# LaserScanner.net
KiCad netlist of a schematic drawn in EAGLE
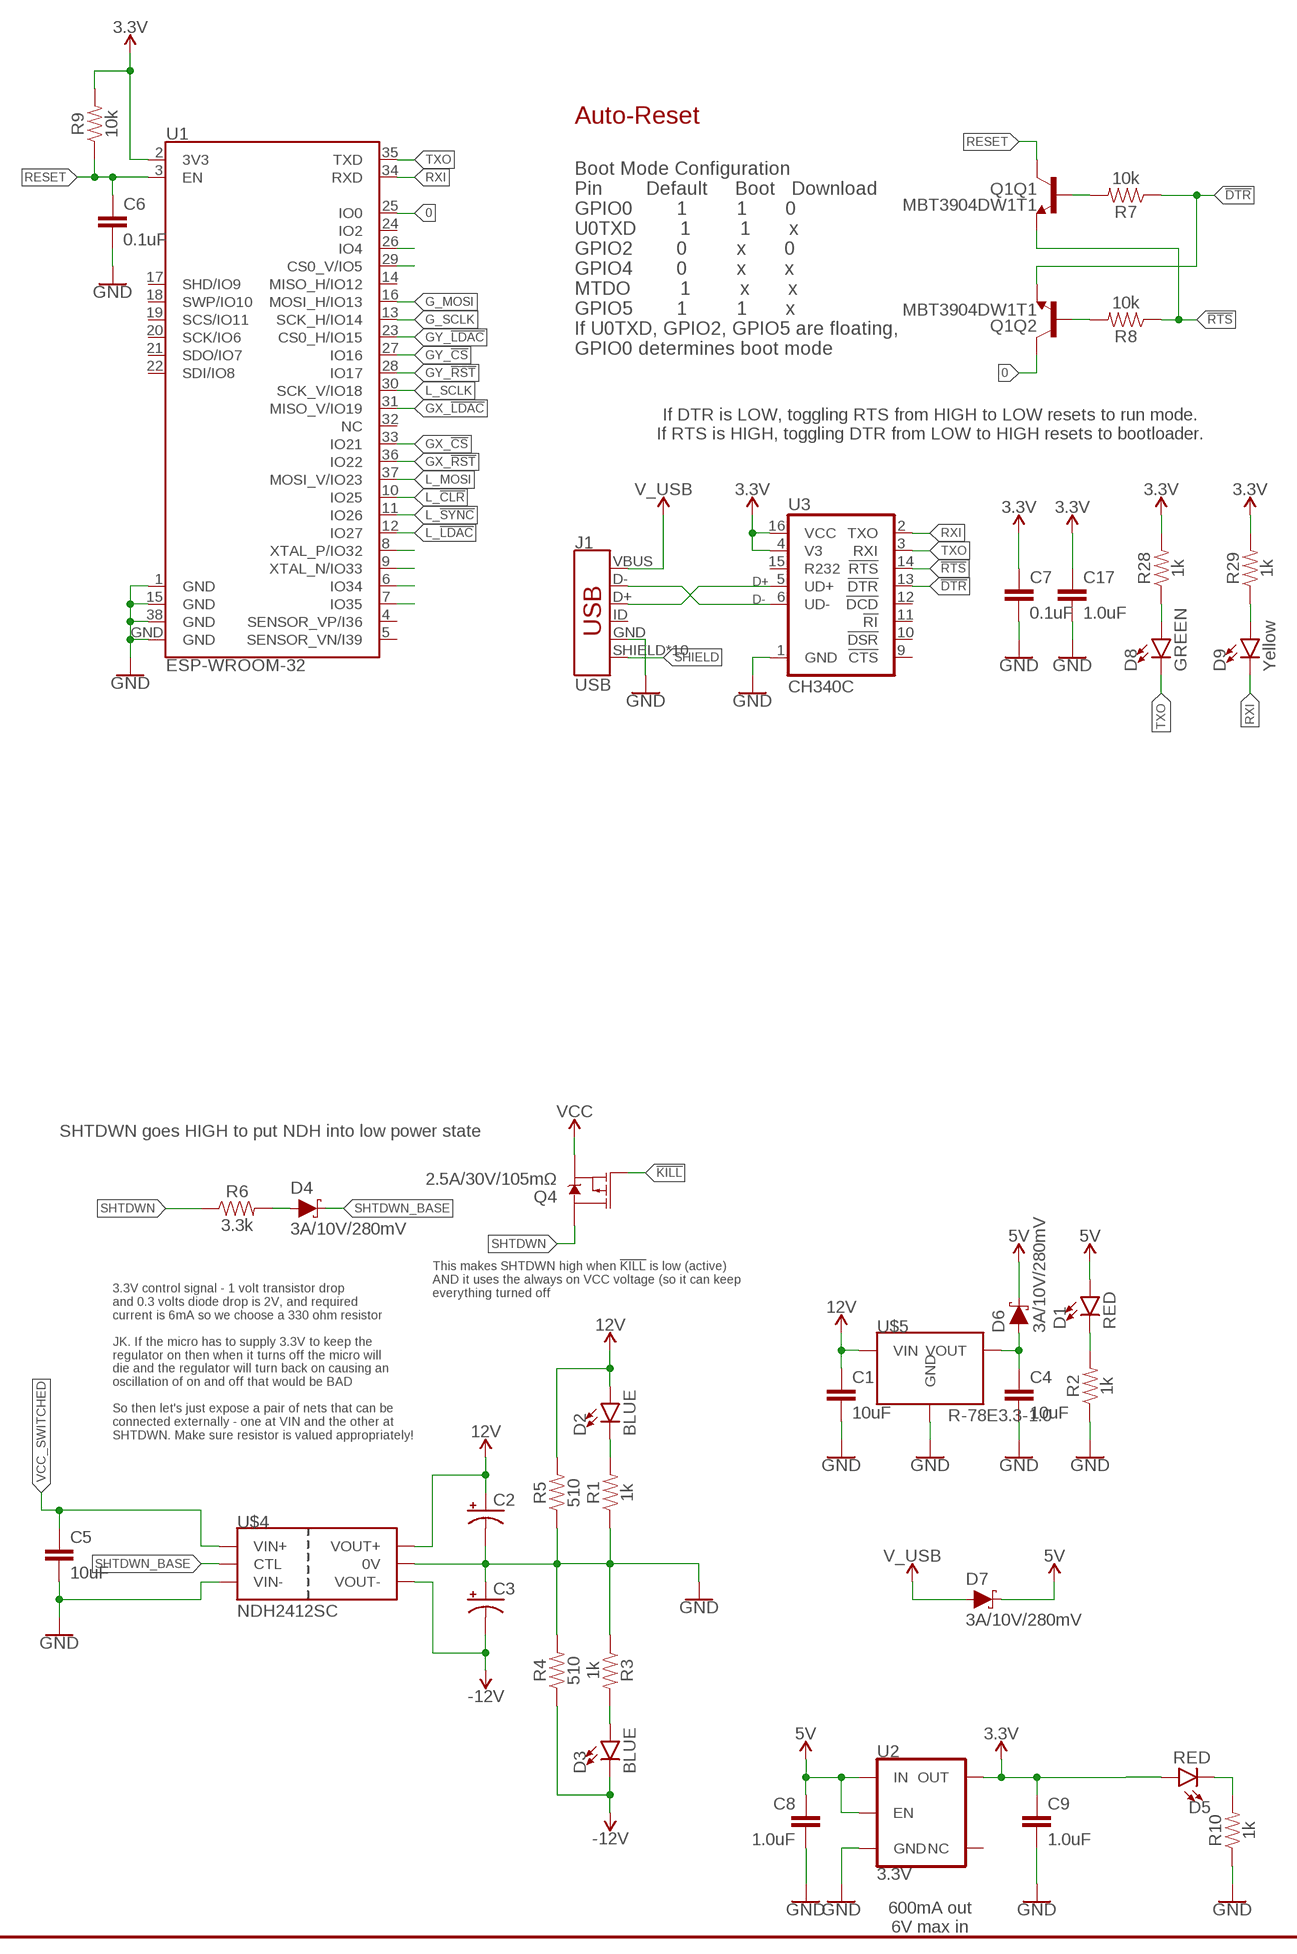
[diagram p0: schematic, sheet 1, part 1 of 2]
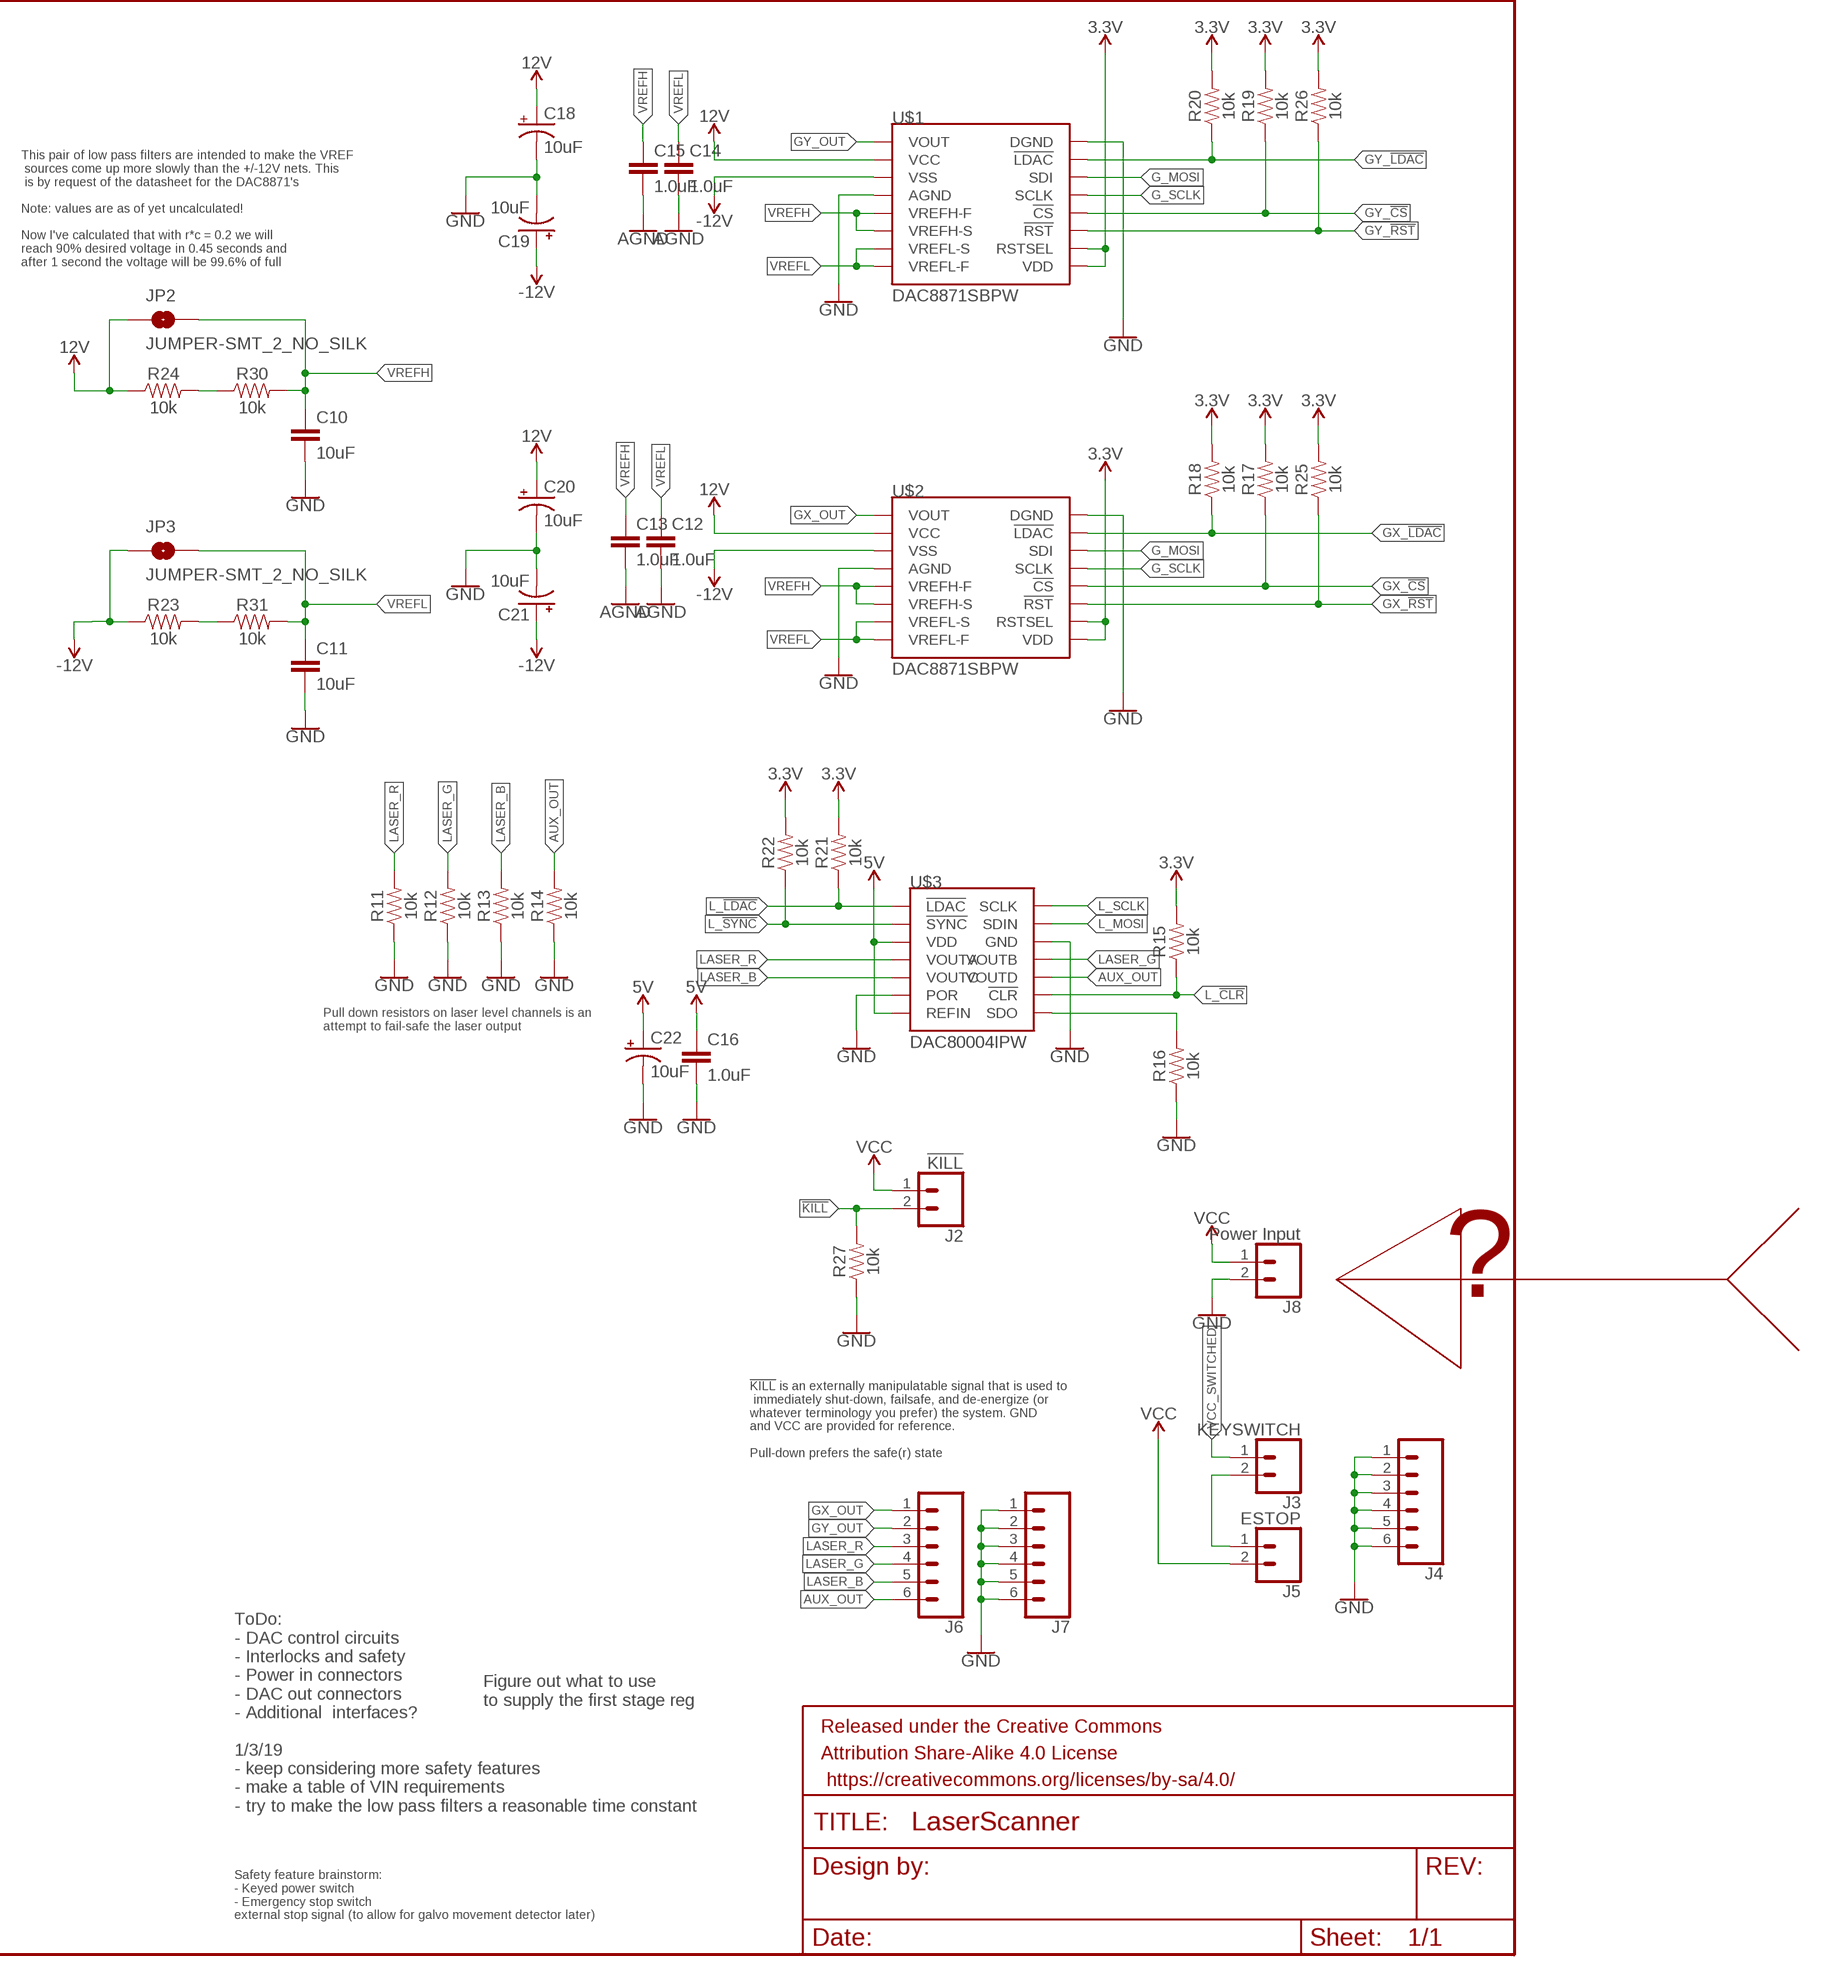
[diagram p1: schematic, sheet 1, part 2 of 2]

(export (version "E")
  (design (tool "Eeschema 10.0.6"))
  (components
    (comp (ref "C1")
      (value "10uF")
      (footprint "eagle-import:1210")
      (libsource (lib "eagle-import") (part "10UF-1210-50V-20%"))
    )
    (comp (ref "C2")
      (value "47UF-POLAR-PANASONIC_D-50V-20%")
      (footprint "eagle-import:PANASONIC_D")
      (libsource (lib "eagle-import") (part "47UF-POLAR-PANASONIC_D-50V-20%"))
    )
    (comp (ref "C3")
      (value "47UF-POLAR-PANASONIC_D-50V-20%")
      (footprint "eagle-import:PANASONIC_D")
      (libsource (lib "eagle-import") (part "47UF-POLAR-PANASONIC_D-50V-20%"))
    )
    (comp (ref "C4")
      (value "10uF")
      (footprint "eagle-import:1210")
      (libsource (lib "eagle-import") (part "10UF-1210-50V-20%"))
    )
    (comp (ref "C5")
      (value "10uF")
      (footprint "eagle-import:1210")
      (libsource (lib "eagle-import") (part "10UF-1210-50V-20%"))
    )
    (comp (ref "C6")
      (value "0.1uF")
      (footprint "eagle-import:0603")
      (libsource (lib "eagle-import") (part "0.1UF-0603-25V-(+80/-20%)"))
    )
    (comp (ref "C7")
      (value "0.1uF")
      (footprint "eagle-import:0603")
      (libsource (lib "eagle-import") (part "0.1UF-0603-25V-5%"))
    )
    (comp (ref "C8")
      (value "1.0uF")
      (footprint "eagle-import:0603")
      (libsource (lib "eagle-import") (part "1.0UF-0603-16V-10%"))
    )
    (comp (ref "C9")
      (value "1.0uF")
      (footprint "eagle-import:0603")
      (libsource (lib "eagle-import") (part "1.0UF-0603-16V-10%"))
    )
    (comp (ref "C10")
      (value "10uF")
      (footprint "eagle-import:1210")
      (libsource (lib "eagle-import") (part "10UF-1210-50V-20%"))
    )
    (comp (ref "C11")
      (value "10uF")
      (footprint "eagle-import:1210")
      (libsource (lib "eagle-import") (part "10UF-1210-50V-20%"))
    )
    (comp (ref "C12")
      (value "1.0uF")
      (footprint "eagle-import:0603")
      (libsource (lib "eagle-import") (part "1.0UF-0603-16V-10%-X7R"))
    )
    (comp (ref "C13")
      (value "1.0uF")
      (footprint "eagle-import:0603")
      (libsource (lib "eagle-import") (part "1.0UF-0603-16V-10%-X7R"))
    )
    (comp (ref "C14")
      (value "1.0uF")
      (footprint "eagle-import:0603")
      (libsource (lib "eagle-import") (part "1.0UF-0603-16V-10%-X7R"))
    )
    (comp (ref "C15")
      (value "1.0uF")
      (footprint "eagle-import:0603")
      (libsource (lib "eagle-import") (part "1.0UF-0603-16V-10%-X7R"))
    )
    (comp (ref "C16")
      (value "1.0uF")
      (footprint "eagle-import:0603")
      (libsource (lib "eagle-import") (part "1.0UF-0603-16V-10%-X7R"))
    )
    (comp (ref "C17")
      (value "1.0uF")
      (footprint "eagle-import:0603")
      (libsource (lib "eagle-import") (part "1.0UF-0603-16V-10%-X7R"))
    )
    (comp (ref "C18")
      (value "10uF")
      (footprint "eagle-import:EIA3216")
      (libsource (lib "eagle-import") (part "10UF-POLAR-EIA3216-16V-10%(TANT)"))
    )
    (comp (ref "C19")
      (value "10uF")
      (footprint "eagle-import:EIA3216")
      (libsource (lib "eagle-import") (part "10UF-POLAR-EIA3216-16V-10%(TANT)"))
    )
    (comp (ref "C20")
      (value "10uF")
      (footprint "eagle-import:EIA3216")
      (libsource (lib "eagle-import") (part "10UF-POLAR-EIA3216-16V-10%(TANT)"))
    )
    (comp (ref "C21")
      (value "10uF")
      (footprint "eagle-import:EIA3216")
      (libsource (lib "eagle-import") (part "10UF-POLAR-EIA3216-16V-10%(TANT)"))
    )
    (comp (ref "C22")
      (value "10uF")
      (footprint "eagle-import:EIA3216")
      (libsource (lib "eagle-import") (part "10UF-POLAR-EIA3216-16V-10%(TANT)"))
    )
    (comp (ref "D1")
      (value "RED")
      (footprint "eagle-import:LED-0603")
      (libsource (lib "eagle-import") (part "LED-RED0603"))
    )
    (comp (ref "D2")
      (value "BLUE")
      (footprint "eagle-import:LED-0603")
      (libsource (lib "eagle-import") (part "LED-BLUE0603"))
    )
    (comp (ref "D3")
      (value "BLUE")
      (footprint "eagle-import:LED-0603")
      (libsource (lib "eagle-import") (part "LED-BLUE0603"))
    )
    (comp (ref "D4")
      (value "3A/10V/280mV")
      (footprint "eagle-import:SOD-323")
      (libsource (lib "eagle-import") (part "DIODE-SCHOTTKY-BAT60A"))
    )
    (comp (ref "D5")
      (value "RED")
      (footprint "eagle-import:LED-0603")
      (libsource (lib "eagle-import") (part "LED-RED0603"))
    )
    (comp (ref "D6")
      (value "3A/10V/280mV")
      (footprint "eagle-import:SOD-323")
      (libsource (lib "eagle-import") (part "DIODE-SCHOTTKY-BAT60A"))
    )
    (comp (ref "D7")
      (value "3A/10V/280mV")
      (footprint "eagle-import:SOD-323")
      (libsource (lib "eagle-import") (part "DIODE-SCHOTTKY-BAT60A"))
    )
    (comp (ref "D8")
      (value "GREEN")
      (footprint "eagle-import:LED-0603")
      (libsource (lib "eagle-import") (part "LED-GREEN0603"))
    )
    (comp (ref "D9")
      (value "Yellow")
      (footprint "eagle-import:LED-0603")
      (libsource (lib "eagle-import") (part "LED-YELLOW0603"))
    )
    (comp (ref "FRAME1")
      (value "FRAME-LEDGER")
      (footprint "eagle-import:CREATIVE_COMMONS")
      (libsource (lib "eagle-import") (part "FRAME-LEDGER"))
    )
    (comp (ref "J1")
      (value "USB")
      (footprint "eagle-import:USB-MICROB-PTH-MILL")
      (libsource (lib "eagle-import") (part "USB_MICRO-B_HALF_PTH_MILL"))
    )
    (comp (ref "J2")
      (value "!KILL!")
      (footprint "eagle-import:1X02_NO_SILK")
      (libsource (lib "eagle-import") (part "CONN_021X02_NO_SILK"))
    )
    (comp (ref "J3")
      (value "KEYSWITCH")
      (footprint "eagle-import:1X02_NO_SILK")
      (libsource (lib "eagle-import") (part "CONN_021X02_NO_SILK"))
    )
    (comp (ref "J4")
      (value "CONN_06NO_SILK_FEMALE_PTH")
      (footprint "eagle-import:1X06_NO_SILK")
      (libsource (lib "eagle-import") (part "CONN_06NO_SILK_FEMALE_PTH"))
    )
    (comp (ref "J5")
      (value "ESTOP")
      (footprint "eagle-import:1X02_NO_SILK")
      (libsource (lib "eagle-import") (part "CONN_021X02_NO_SILK"))
    )
    (comp (ref "J6")
      (value "CONN_06NO_SILK_FEMALE_PTH")
      (footprint "eagle-import:1X06_NO_SILK")
      (libsource (lib "eagle-import") (part "CONN_06NO_SILK_FEMALE_PTH"))
    )
    (comp (ref "J7")
      (value "CONN_06NO_SILK_FEMALE_PTH")
      (footprint "eagle-import:1X06_NO_SILK")
      (libsource (lib "eagle-import") (part "CONN_06NO_SILK_FEMALE_PTH"))
    )
    (comp (ref "J8")
      (value "Power Input")
      (footprint "eagle-import:1X02_NO_SILK")
      (libsource (lib "eagle-import") (part "CONN_021X02_NO_SILK"))
    )
    (comp (ref "JP2")
      (value "JUMPER-SMT_2_NO_SILK")
      (footprint "eagle-import:SMT-JUMPER_2_NO_SILK")
      (libsource (lib "eagle-import") (part "JUMPER-SMT_2_NO_SILK"))
    )
    (comp (ref "JP3")
      (value "JUMPER-SMT_2_NO_SILK")
      (footprint "eagle-import:SMT-JUMPER_2_NO_SILK")
      (libsource (lib "eagle-import") (part "JUMPER-SMT_2_NO_SILK"))
    )
    (comp (ref "Q1")
      (value "MBT3904DW1T1")
      (footprint "eagle-import:SC70-6")
      (libsource (lib "eagle-import") (part "TRANS_NPN_DUAL-MBT3904DW1T1"))
    )
    (comp (ref "Q4")
      (value "2.5A/30V/105mΩ")
      (footprint "eagle-import:SOT23-3")
      (libsource (lib "eagle-import") (part "MOSFET_PCH-DMG2307L"))
    )
    (comp (ref "R1")
      (value "1k")
      (footprint "eagle-import:0603")
      (libsource (lib "eagle-import") (part "1KOHM-0603-1/10W-1%"))
    )
    (comp (ref "R2")
      (value "1k")
      (footprint "eagle-import:0603")
      (libsource (lib "eagle-import") (part "1KOHM-0603-1/10W-1%"))
    )
    (comp (ref "R3")
      (value "1k")
      (footprint "eagle-import:0603")
      (libsource (lib "eagle-import") (part "1KOHM-0603-1/10W-1%"))
    )
    (comp (ref "R4")
      (value "510")
      (footprint "eagle-import:2010")
      (libsource (lib "eagle-import") (part "510OHM-2010-1/2W-5%"))
    )
    (comp (ref "R5")
      (value "510")
      (footprint "eagle-import:2010")
      (libsource (lib "eagle-import") (part "510OHM-2010-1/2W-5%"))
    )
    (comp (ref "R6")
      (value "3.3k")
      (footprint "eagle-import:0603")
      (libsource (lib "eagle-import") (part "3.3KOHM-0603-1/10W-1%"))
    )
    (comp (ref "R7")
      (value "10k")
      (footprint "eagle-import:0603")
      (libsource (lib "eagle-import") (part "10KOHM-0603-1/10W-1%"))
    )
    (comp (ref "R8")
      (value "10k")
      (footprint "eagle-import:0603")
      (libsource (lib "eagle-import") (part "10KOHM-0603-1/10W-1%"))
    )
    (comp (ref "R9")
      (value "10k")
      (footprint "eagle-import:0603")
      (libsource (lib "eagle-import") (part "10KOHM-0603-1/10W-1%"))
    )
    (comp (ref "R10")
      (value "1k")
      (footprint "eagle-import:0603")
      (libsource (lib "eagle-import") (part "1KOHM-0603-1/10W-1%"))
    )
    (comp (ref "R11")
      (value "10k")
      (footprint "eagle-import:0603")
      (libsource (lib "eagle-import") (part "10KOHM-0603-1/10W-1%"))
    )
    (comp (ref "R12")
      (value "10k")
      (footprint "eagle-import:0603")
      (libsource (lib "eagle-import") (part "10KOHM-0603-1/10W-1%"))
    )
    (comp (ref "R13")
      (value "10k")
      (footprint "eagle-import:0603")
      (libsource (lib "eagle-import") (part "10KOHM-0603-1/10W-1%"))
    )
    (comp (ref "R14")
      (value "10k")
      (footprint "eagle-import:0603")
      (libsource (lib "eagle-import") (part "10KOHM-0603-1/10W-1%"))
    )
    (comp (ref "R15")
      (value "10k")
      (footprint "eagle-import:0603")
      (libsource (lib "eagle-import") (part "10KOHM-0603-1/10W-1%"))
    )
    (comp (ref "R16")
      (value "10k")
      (footprint "eagle-import:0603")
      (libsource (lib "eagle-import") (part "10KOHM-0603-1/10W-1%"))
    )
    (comp (ref "R17")
      (value "10k")
      (footprint "eagle-import:0603")
      (libsource (lib "eagle-import") (part "10KOHM-0603-1/10W-1%"))
    )
    (comp (ref "R18")
      (value "10k")
      (footprint "eagle-import:0603")
      (libsource (lib "eagle-import") (part "10KOHM-0603-1/10W-1%"))
    )
    (comp (ref "R19")
      (value "10k")
      (footprint "eagle-import:0603")
      (libsource (lib "eagle-import") (part "10KOHM-0603-1/10W-1%"))
    )
    (comp (ref "R20")
      (value "10k")
      (footprint "eagle-import:0603")
      (libsource (lib "eagle-import") (part "10KOHM-0603-1/10W-1%"))
    )
    (comp (ref "R21")
      (value "10k")
      (footprint "eagle-import:0603")
      (libsource (lib "eagle-import") (part "10KOHM-0603-1/10W-1%"))
    )
    (comp (ref "R22")
      (value "10k")
      (footprint "eagle-import:0603")
      (libsource (lib "eagle-import") (part "10KOHM-0603-1/10W-1%"))
    )
    (comp (ref "R23")
      (value "10k")
      (footprint "eagle-import:0603")
      (libsource (lib "eagle-import") (part "10KOHM-0603-1/10W-1%"))
    )
    (comp (ref "R24")
      (value "10k")
      (footprint "eagle-import:0603")
      (libsource (lib "eagle-import") (part "10KOHM-0603-1/10W-1%"))
    )
    (comp (ref "R25")
      (value "10k")
      (footprint "eagle-import:0603")
      (libsource (lib "eagle-import") (part "10KOHM-0603-1/10W-1%"))
    )
    (comp (ref "R26")
      (value "10k")
      (footprint "eagle-import:0603")
      (libsource (lib "eagle-import") (part "10KOHM-0603-1/10W-1%"))
    )
    (comp (ref "R27")
      (value "10k")
      (footprint "eagle-import:0603")
      (libsource (lib "eagle-import") (part "10KOHM-0603-1/10W-1%"))
    )
    (comp (ref "R28")
      (value "1k")
      (footprint "eagle-import:0603")
      (libsource (lib "eagle-import") (part "1KOHM-0603-1/10W-1%"))
    )
    (comp (ref "R29")
      (value "1k")
      (footprint "eagle-import:0603")
      (libsource (lib "eagle-import") (part "1KOHM-0603-1/10W-1%"))
    )
    (comp (ref "R30")
      (value "10k")
      (footprint "eagle-import:0603")
      (libsource (lib "eagle-import") (part "10KOHM-0603-1/10W-1%"))
    )
    (comp (ref "R31")
      (value "10k")
      (footprint "eagle-import:0603")
      (libsource (lib "eagle-import") (part "10KOHM-0603-1/10W-1%"))
    )
    (comp (ref "U$1")
      (value "DAC8871SBPW")
      (footprint "eagle-import:TSSOP16")
      (libsource (lib "eagle-import") (part "DAC8871SBPW"))
    )
    (comp (ref "U$2")
      (value "DAC8871SBPW")
      (footprint "eagle-import:TSSOP16")
      (libsource (lib "eagle-import") (part "DAC8871SBPW"))
    )
    (comp (ref "U$3")
      (value "DAC80004IPW")
      (footprint "eagle-import:TSSOP14")
      (libsource (lib "eagle-import") (part "DAC80004IPW"))
    )
    (comp (ref "U$4")
      (value "NDH2412SC")
      (footprint "eagle-import:NDH")
      (libsource (lib "eagle-import") (part "NDH2412SC"))
    )
    (comp (ref "U$5")
      (value "R-78E3.3-1.0")
      (footprint "eagle-import:RE-78E")
      (libsource (lib "eagle-import") (part "R-78E3.3-1.0"))
    )
    (comp (ref "U1")
      (value "ESP-WROOM-32")
      (footprint "eagle-import:ESP-WROOM-32")
      (libsource (lib "eagle-import") (part "ESP-WROOM-32"))
    )
    (comp (ref "U2")
      (value "3.3V")
      (footprint "eagle-import:SOT23-5")
      (libsource (lib "eagle-import") (part "V_REG_AP2112K-3.3V"))
    )
    (comp (ref "U3")
      (value "CH340C")
      (footprint "eagle-import:SO016")
      (libsource (lib "eagle-import") (part "CH340C"))
    )
  )
  (nets
    (net (code "1") (name "-12V") (class "Default")
      (node (ref "C19") (pin "+") (pinfunction "+_+") (pintype "passive"))
      (node (ref "C21") (pin "+") (pinfunction "+_+") (pintype "passive"))
      (node (ref "C3") (pin "-") (pinfunction "-_-") (pintype "passive"))
      (node (ref "D3") (pin "C") (pinfunction "C_C") (pintype "passive"))
      (node (ref "JP3") (pin "1") (pinfunction "1_1") (pintype "passive"))
      (node (ref "R23") (pin "1") (pinfunction "1_1") (pintype "passive"))
      (node (ref "R4") (pin "1") (pinfunction "1_1") (pintype "passive"))
      (node (ref "U$1") (pin "3") (pinfunction "VSS_3") (pintype "bidirectional"))
      (node (ref "U$2") (pin "3") (pinfunction "VSS_3") (pintype "bidirectional"))
      (node (ref "U$4") (pin "9") (pinfunction "VOUT-_9") (pintype "bidirectional"))
    )
    (net (code "2") (name "/D+") (class "Default")
      (node (ref "J1") (pin "D+") (pinfunction "D+_D+") (pintype "bidirectional"))
      (node (ref "U3") (pin "5") (pinfunction "UD+_5") (pintype "bidirectional"))
    )
    (net (code "3") (name "/D-") (class "Default")
      (node (ref "J1") (pin "D-") (pinfunction "D-_D-") (pintype "bidirectional"))
      (node (ref "U3") (pin "6") (pinfunction "UD-_6") (pintype "bidirectional"))
    )
    (net (code "4") (name "/GX_~{CS}") (class "Default")
      (node (ref "R17") (pin "1") (pinfunction "1_1") (pintype "passive"))
      (node (ref "U$2") (pin "12") (pinfunction "~{CS}_12") (pintype "bidirectional"))
      (node (ref "U1") (pin "33") (pinfunction "IO21_33") (pintype "bidirectional"))
    )
    (net (code "5") (name "/GX_~{LDAC}") (class "Default")
      (node (ref "R18") (pin "1") (pinfunction "1_1") (pintype "passive"))
      (node (ref "U$2") (pin "15") (pinfunction "~{LDAC}_15") (pintype "bidirectional"))
      (node (ref "U1") (pin "31") (pinfunction "MISO_V/IO19_31") (pintype "bidirectional"))
    )
    (net (code "6") (name "/GX_~{RST}") (class "Default")
      (node (ref "R25") (pin "1") (pinfunction "1_1") (pintype "passive"))
      (node (ref "U$2") (pin "11") (pinfunction "~{RST}_11") (pintype "bidirectional"))
      (node (ref "U1") (pin "36") (pinfunction "IO22_36") (pintype "bidirectional"))
    )
    (net (code "7") (name "/GY_~{CS}") (class "Default")
      (node (ref "R19") (pin "1") (pinfunction "1_1") (pintype "passive"))
      (node (ref "U$1") (pin "12") (pinfunction "~{CS}_12") (pintype "bidirectional"))
      (node (ref "U1") (pin "27") (pinfunction "IO16_27") (pintype "bidirectional"))
    )
    (net (code "8") (name "/GY_~{LDAC}") (class "Default")
      (node (ref "R20") (pin "1") (pinfunction "1_1") (pintype "passive"))
      (node (ref "U$1") (pin "15") (pinfunction "~{LDAC}_15") (pintype "bidirectional"))
      (node (ref "U1") (pin "23") (pinfunction "CS0_H/IO15_23") (pintype "bidirectional"))
    )
    (net (code "9") (name "/GY_~{RST}") (class "Default")
      (node (ref "R26") (pin "1") (pinfunction "1_1") (pintype "passive"))
      (node (ref "U$1") (pin "11") (pinfunction "~{RST}_11") (pintype "bidirectional"))
      (node (ref "U1") (pin "28") (pinfunction "IO17_28") (pintype "bidirectional"))
    )
    (net (code "10") (name "/L_~{CLR}") (class "Default")
      (node (ref "R15") (pin "1") (pinfunction "1_1") (pintype "passive"))
      (node (ref "U$3") (pin "9") (pinfunction "~{CLR}_9") (pintype "bidirectional"))
      (node (ref "U1") (pin "10") (pinfunction "IO25_10") (pintype "bidirectional"))
    )
    (net (code "11") (name "/L_~{LDAC}") (class "Default")
      (node (ref "R21") (pin "1") (pinfunction "1_1") (pintype "passive"))
      (node (ref "U$3") (pin "1") (pinfunction "~{LDAC}_1") (pintype "bidirectional"))
      (node (ref "U1") (pin "12") (pinfunction "IO27_12") (pintype "bidirectional"))
    )
    (net (code "12") (name "/L_~{SYNC}") (class "Default")
      (node (ref "R22") (pin "1") (pinfunction "1_1") (pintype "passive"))
      (node (ref "U$3") (pin "2") (pinfunction "~{SYNC}_2") (pintype "bidirectional"))
      (node (ref "U1") (pin "11") (pinfunction "IO26_11") (pintype "bidirectional"))
    )
    (net (code "13") (name "/~{DTR}") (class "Default")
      (node (ref "Q1") (pin "1") (pinfunction "E_1") (pintype "passive"))
      (node (ref "R7") (pin "1") (pinfunction "1_1") (pintype "passive"))
      (node (ref "U3") (pin "13") (pinfunction "~{DTR}_13") (pintype "bidirectional"))
    )
    (net (code "14") (name "/~{KILL}") (class "Default")
      (node (ref "J2") (pin "2") (pinfunction "2_2") (pintype "passive"))
      (node (ref "Q4") (pin "1") (pinfunction "G_1") (pintype "bidirectional"))
      (node (ref "R27") (pin "2") (pinfunction "2_2") (pintype "passive"))
    )
    (net (code "15") (name "/~{RTS}") (class "Default")
      (node (ref "Q1") (pin "4") (pinfunction "E_4") (pintype "passive"))
      (node (ref "R8") (pin "1") (pinfunction "1_1") (pintype "passive"))
      (node (ref "U3") (pin "14") (pinfunction "~{RTS}_14") (pintype "bidirectional"))
    )
    (net (code "16") (name "0") (class "Default")
      (node (ref "Q1") (pin "6") (pinfunction "C_6") (pintype "passive"))
      (node (ref "U1") (pin "25") (pinfunction "IO0_25") (pintype "bidirectional"))
    )
    (net (code "17") (name "3.3V") (class "Default")
      (node (ref "C17") (pin "1") (pinfunction "1_1") (pintype "passive"))
      (node (ref "C7") (pin "1") (pinfunction "1_1") (pintype "passive"))
      (node (ref "C9") (pin "1") (pinfunction "1_1") (pintype "passive"))
      (node (ref "D5") (pin "A") (pinfunction "A_A") (pintype "passive"))
      (node (ref "R15") (pin "2") (pinfunction "2_2") (pintype "passive"))
      (node (ref "R17") (pin "2") (pinfunction "2_2") (pintype "passive"))
      (node (ref "R18") (pin "2") (pinfunction "2_2") (pintype "passive"))
      (node (ref "R19") (pin "2") (pinfunction "2_2") (pintype "passive"))
      (node (ref "R20") (pin "2") (pinfunction "2_2") (pintype "passive"))
      (node (ref "R21") (pin "2") (pinfunction "2_2") (pintype "passive"))
      (node (ref "R22") (pin "2") (pinfunction "2_2") (pintype "passive"))
      (node (ref "R25") (pin "2") (pinfunction "2_2") (pintype "passive"))
      (node (ref "R26") (pin "2") (pinfunction "2_2") (pintype "passive"))
      (node (ref "R28") (pin "2") (pinfunction "2_2") (pintype "passive"))
      (node (ref "R29") (pin "2") (pinfunction "2_2") (pintype "passive"))
      (node (ref "R9") (pin "2") (pinfunction "2_2") (pintype "passive"))
      (node (ref "U$1") (pin "10") (pinfunction "RSTSEL_10") (pintype "bidirectional"))
      (node (ref "U$1") (pin "9") (pinfunction "VDD_9") (pintype "bidirectional"))
      (node (ref "U$2") (pin "10") (pinfunction "RSTSEL_10") (pintype "bidirectional"))
      (node (ref "U$2") (pin "9") (pinfunction "VDD_9") (pintype "bidirectional"))
      (node (ref "U1") (pin "2") (pinfunction "3V3_2") (pintype "bidirectional"))
      (node (ref "U2") (pin "5") (pinfunction "OUT_5") (pintype "passive"))
      (node (ref "U3") (pin "16") (pinfunction "VCC_16") (pintype "bidirectional"))
      (node (ref "U3") (pin "4") (pinfunction "V3_4") (pintype "bidirectional"))
    )
    (net (code "18") (name "5V") (class "Default")
      (node (ref "C16") (pin "1") (pinfunction "1_1") (pintype "passive"))
      (node (ref "C22") (pin "+") (pinfunction "+_+") (pintype "passive"))
      (node (ref "C8") (pin "1") (pinfunction "1_1") (pintype "passive"))
      (node (ref "D1") (pin "A") (pinfunction "A_A") (pintype "passive"))
      (node (ref "D6") (pin "C") (pinfunction "C_C") (pintype "passive"))
      (node (ref "D7") (pin "C") (pinfunction "C_C") (pintype "passive"))
      (node (ref "U$3") (pin "3") (pinfunction "VDD_3") (pintype "bidirectional"))
      (node (ref "U$3") (pin "7") (pinfunction "REFIN_7") (pintype "bidirectional"))
      (node (ref "U2") (pin "1") (pinfunction "IN_1") (pintype "input"))
      (node (ref "U2") (pin "3") (pinfunction "EN_3") (pintype "input"))
    )
    (net (code "19") (name "12V") (class "Default")
      (node (ref "C1") (pin "1") (pinfunction "1_1") (pintype "passive"))
      (node (ref "C18") (pin "+") (pinfunction "+_+") (pintype "passive"))
      (node (ref "C2") (pin "+") (pinfunction "+_+") (pintype "passive"))
      (node (ref "C20") (pin "+") (pinfunction "+_+") (pintype "passive"))
      (node (ref "D2") (pin "A") (pinfunction "A_A") (pintype "passive"))
      (node (ref "JP2") (pin "1") (pinfunction "1_1") (pintype "passive"))
      (node (ref "R24") (pin "1") (pinfunction "1_1") (pintype "passive"))
      (node (ref "R5") (pin "2") (pinfunction "2_2") (pintype "passive"))
      (node (ref "U$1") (pin "2") (pinfunction "VCC_2") (pintype "bidirectional"))
      (node (ref "U$2") (pin "2") (pinfunction "VCC_2") (pintype "bidirectional"))
      (node (ref "U$4") (pin "6") (pinfunction "VOUT+_6") (pintype "bidirectional"))
      (node (ref "U$5") (pin "1") (pinfunction "VIN_1") (pintype "bidirectional"))
    )
    (net (code "20") (name "AGND") (class "Default")
      (node (ref "C12") (pin "2") (pinfunction "2_2") (pintype "passive"))
      (node (ref "C13") (pin "2") (pinfunction "2_2") (pintype "passive"))
      (node (ref "C14") (pin "2") (pinfunction "2_2") (pintype "passive"))
      (node (ref "C15") (pin "2") (pinfunction "2_2") (pintype "passive"))
    )
    (net (code "21") (name "AUX_OUT") (class "Default")
      (node (ref "J6") (pin "6") (pinfunction "6_6") (pintype "passive"))
      (node (ref "R14") (pin "2") (pinfunction "2_2") (pintype "passive"))
      (node (ref "U$3") (pin "10") (pinfunction "VOUTD_10") (pintype "bidirectional"))
    )
    (net (code "22") (name "GND") (class "Default")
      (node (ref "C1") (pin "2") (pinfunction "2_2") (pintype "passive"))
      (node (ref "C10") (pin "2") (pinfunction "2_2") (pintype "passive"))
      (node (ref "C11") (pin "2") (pinfunction "2_2") (pintype "passive"))
      (node (ref "C16") (pin "2") (pinfunction "2_2") (pintype "passive"))
      (node (ref "C17") (pin "2") (pinfunction "2_2") (pintype "passive"))
      (node (ref "C18") (pin "-") (pinfunction "-_-") (pintype "passive"))
      (node (ref "C19") (pin "-") (pinfunction "-_-") (pintype "passive"))
      (node (ref "C2") (pin "-") (pinfunction "-_-") (pintype "passive"))
      (node (ref "C20") (pin "-") (pinfunction "-_-") (pintype "passive"))
      (node (ref "C21") (pin "-") (pinfunction "-_-") (pintype "passive"))
      (node (ref "C22") (pin "-") (pinfunction "-_-") (pintype "passive"))
      (node (ref "C3") (pin "+") (pinfunction "+_+") (pintype "passive"))
      (node (ref "C4") (pin "2") (pinfunction "2_2") (pintype "passive"))
      (node (ref "C5") (pin "2") (pinfunction "2_2") (pintype "passive"))
      (node (ref "C6") (pin "2") (pinfunction "2_2") (pintype "passive"))
      (node (ref "C7") (pin "2") (pinfunction "2_2") (pintype "passive"))
      (node (ref "C8") (pin "2") (pinfunction "2_2") (pintype "passive"))
      (node (ref "C9") (pin "2") (pinfunction "2_2") (pintype "passive"))
      (node (ref "J1") (pin "GND") (pinfunction "GND_GND") (pintype "power_in"))
      (node (ref "J4") (pin "1") (pinfunction "1_1") (pintype "passive"))
      (node (ref "J4") (pin "2") (pinfunction "2_2") (pintype "passive"))
      (node (ref "J4") (pin "3") (pinfunction "3_3") (pintype "passive"))
      (node (ref "J4") (pin "4") (pinfunction "4_4") (pintype "passive"))
      (node (ref "J4") (pin "5") (pinfunction "5_5") (pintype "passive"))
      (node (ref "J4") (pin "6") (pinfunction "6_6") (pintype "passive"))
      (node (ref "J7") (pin "1") (pinfunction "1_1") (pintype "passive"))
      (node (ref "J7") (pin "2") (pinfunction "2_2") (pintype "passive"))
      (node (ref "J7") (pin "3") (pinfunction "3_3") (pintype "passive"))
      (node (ref "J7") (pin "4") (pinfunction "4_4") (pintype "passive"))
      (node (ref "J7") (pin "5") (pinfunction "5_5") (pintype "passive"))
      (node (ref "J7") (pin "6") (pinfunction "6_6") (pintype "passive"))
      (node (ref "J8") (pin "2") (pinfunction "2_2") (pintype "passive"))
      (node (ref "R1") (pin "1") (pinfunction "1_1") (pintype "passive"))
      (node (ref "R10") (pin "1") (pinfunction "1_1") (pintype "passive"))
      (node (ref "R11") (pin "1") (pinfunction "1_1") (pintype "passive"))
      (node (ref "R12") (pin "1") (pinfunction "1_1") (pintype "passive"))
      (node (ref "R13") (pin "1") (pinfunction "1_1") (pintype "passive"))
      (node (ref "R14") (pin "1") (pinfunction "1_1") (pintype "passive"))
      (node (ref "R16") (pin "1") (pinfunction "1_1") (pintype "passive"))
      (node (ref "R2") (pin "1") (pinfunction "1_1") (pintype "passive"))
      (node (ref "R27") (pin "1") (pinfunction "1_1") (pintype "passive"))
      (node (ref "R3") (pin "1") (pinfunction "1_1") (pintype "passive"))
      (node (ref "R4") (pin "2") (pinfunction "2_2") (pintype "passive"))
      (node (ref "R5") (pin "1") (pinfunction "1_1") (pintype "passive"))
      (node (ref "U$1") (pin "16") (pinfunction "DGND_16") (pintype "bidirectional"))
      (node (ref "U$1") (pin "4") (pinfunction "AGND_4") (pintype "bidirectional"))
      (node (ref "U$2") (pin "16") (pinfunction "DGND_16") (pintype "bidirectional"))
      (node (ref "U$2") (pin "4") (pinfunction "AGND_4") (pintype "bidirectional"))
      (node (ref "U$3") (pin "12") (pinfunction "GND_12") (pintype "bidirectional"))
      (node (ref "U$3") (pin "6") (pinfunction "POR_6") (pintype "bidirectional"))
      (node (ref "U$4") (pin "1") (pinfunction "VIN-_1") (pintype "bidirectional"))
      (node (ref "U$4") (pin "7") (pinfunction "0V_7") (pintype "bidirectional"))
      (node (ref "U$5") (pin "2") (pinfunction "GND_2") (pintype "bidirectional"))
      (node (ref "U1") (pin "1") (pinfunction "GND_1") (pintype "bidirectional"))
      (node (ref "U1") (pin "15") (pinfunction "GND_15") (pintype "bidirectional"))
      (node (ref "U1") (pin "38") (pinfunction "GND_38") (pintype "bidirectional"))
      (node (ref "U1") (pin "GND") (pinfunction "GND_GND") (pintype "bidirectional"))
      (node (ref "U2") (pin "2") (pinfunction "GND_2") (pintype "input"))
      (node (ref "U3") (pin "1") (pinfunction "GND_1") (pintype "bidirectional"))
    )
    (net (code "23") (name "GX_OUT") (class "Default")
      (node (ref "J6") (pin "1") (pinfunction "1_1") (pintype "passive"))
      (node (ref "U$2") (pin "1") (pinfunction "VOUT_1") (pintype "bidirectional"))
    )
    (net (code "24") (name "GY_OUT") (class "Default")
      (node (ref "J6") (pin "2") (pinfunction "2_2") (pintype "passive"))
      (node (ref "U$1") (pin "1") (pinfunction "VOUT_1") (pintype "bidirectional"))
    )
    (net (code "25") (name "G_MOSI") (class "Default")
      (node (ref "U$1") (pin "14") (pinfunction "SDI_14") (pintype "bidirectional"))
      (node (ref "U$2") (pin "14") (pinfunction "SDI_14") (pintype "bidirectional"))
      (node (ref "U1") (pin "16") (pinfunction "MOSI_H/IO13_16") (pintype "bidirectional"))
    )
    (net (code "26") (name "G_SCLK") (class "Default")
      (node (ref "U$1") (pin "13") (pinfunction "SCLK_13") (pintype "bidirectional"))
      (node (ref "U$2") (pin "13") (pinfunction "SCLK_13") (pintype "bidirectional"))
      (node (ref "U1") (pin "13") (pinfunction "SCK_H/IO14_13") (pintype "bidirectional"))
    )
    (net (code "27") (name "LASER_B") (class "Default")
      (node (ref "J6") (pin "5") (pinfunction "5_5") (pintype "passive"))
      (node (ref "R13") (pin "2") (pinfunction "2_2") (pintype "passive"))
      (node (ref "U$3") (pin "5") (pinfunction "VOUTC_5") (pintype "bidirectional"))
    )
    (net (code "28") (name "LASER_G") (class "Default")
      (node (ref "J6") (pin "4") (pinfunction "4_4") (pintype "passive"))
      (node (ref "R12") (pin "2") (pinfunction "2_2") (pintype "passive"))
      (node (ref "U$3") (pin "11") (pinfunction "VOUTB_11") (pintype "bidirectional"))
    )
    (net (code "29") (name "LASER_R") (class "Default")
      (node (ref "J6") (pin "3") (pinfunction "3_3") (pintype "passive"))
      (node (ref "R11") (pin "2") (pinfunction "2_2") (pintype "passive"))
      (node (ref "U$3") (pin "4") (pinfunction "VOUTA_4") (pintype "bidirectional"))
    )
    (net (code "30") (name "L_MOSI") (class "Default")
      (node (ref "U$3") (pin "13") (pinfunction "SDIN_13") (pintype "bidirectional"))
      (node (ref "U1") (pin "37") (pinfunction "MOSI_V/IO23_37") (pintype "bidirectional"))
    )
    (net (code "31") (name "L_SCLK") (class "Default")
      (node (ref "U$3") (pin "14") (pinfunction "SCLK_14") (pintype "bidirectional"))
      (node (ref "U1") (pin "30") (pinfunction "SCK_V/IO18_30") (pintype "bidirectional"))
    )
    (net (code "32") (name "Net-(D1-PadC)") (class "Default")
      (node (ref "D1") (pin "C") (pinfunction "C_C") (pintype "passive"))
      (node (ref "R2") (pin "2") (pinfunction "2_2") (pintype "passive"))
    )
    (net (code "33") (name "Net-(D2-PadC)") (class "Default")
      (node (ref "D2") (pin "C") (pinfunction "C_C") (pintype "passive"))
      (node (ref "R1") (pin "2") (pinfunction "2_2") (pintype "passive"))
    )
    (net (code "34") (name "Net-(D3-PadA)") (class "Default")
      (node (ref "D3") (pin "A") (pinfunction "A_A") (pintype "passive"))
      (node (ref "R3") (pin "2") (pinfunction "2_2") (pintype "passive"))
    )
    (net (code "35") (name "Net-(D4-PadA)") (class "Default")
      (node (ref "D4") (pin "A") (pinfunction "A_A") (pintype "passive"))
      (node (ref "R6") (pin "2") (pinfunction "2_2") (pintype "passive"))
    )
    (net (code "36") (name "Net-(D5-PadC)") (class "Default")
      (node (ref "D5") (pin "C") (pinfunction "C_C") (pintype "passive"))
      (node (ref "R10") (pin "2") (pinfunction "2_2") (pintype "passive"))
    )
    (net (code "37") (name "Net-(D8-PadA)") (class "Default")
      (node (ref "D8") (pin "A") (pinfunction "A_A") (pintype "passive"))
      (node (ref "R28") (pin "1") (pinfunction "1_1") (pintype "passive"))
    )
    (net (code "38") (name "Net-(D9-PadA)") (class "Default")
      (node (ref "D9") (pin "A") (pinfunction "A_A") (pintype "passive"))
      (node (ref "R29") (pin "1") (pinfunction "1_1") (pintype "passive"))
    )
    (net (code "39") (name "Net-(J3-Pad2)") (class "Default")
      (node (ref "J3") (pin "2") (pinfunction "2_2") (pintype "passive"))
      (node (ref "J5") (pin "1") (pinfunction "1_1") (pintype "passive"))
    )
    (net (code "40") (name "Net-(Q1A-B)") (class "Default")
      (node (ref "Q1") (pin "5") (pinfunction "B_5") (pintype "passive"))
      (node (ref "R7") (pin "2") (pinfunction "2_2") (pintype "passive"))
    )
    (net (code "41") (name "Net-(Q1B-B)") (class "Default")
      (node (ref "Q1") (pin "2") (pinfunction "B_2") (pintype "passive"))
      (node (ref "R8") (pin "2") (pinfunction "2_2") (pintype "passive"))
    )
    (net (code "42") (name "Net-(R23-Pad2)") (class "Default")
      (node (ref "R23") (pin "2") (pinfunction "2_2") (pintype "passive"))
      (node (ref "R31") (pin "1") (pinfunction "1_1") (pintype "passive"))
    )
    (net (code "43") (name "Net-(R24-Pad2)") (class "Default")
      (node (ref "R24") (pin "2") (pinfunction "2_2") (pintype "passive"))
      (node (ref "R30") (pin "1") (pinfunction "1_1") (pintype "passive"))
    )
    (net (code "44") (name "Net-(U$3-SDO)") (class "Default")
      (node (ref "R16") (pin "2") (pinfunction "2_2") (pintype "passive"))
      (node (ref "U$3") (pin "8") (pinfunction "SDO_8") (pintype "bidirectional"))
    )
    (net (code "45") (name "Net-(U$5-VOUT)") (class "Default")
      (node (ref "C4") (pin "1") (pinfunction "1_1") (pintype "passive"))
      (node (ref "D6") (pin "A") (pinfunction "A_A") (pintype "passive"))
      (node (ref "U$5") (pin "3") (pinfunction "VOUT_3") (pintype "bidirectional"))
    )
    (net (code "46") (name "RESET") (class "Default")
      (node (ref "C6") (pin "1") (pinfunction "1_1") (pintype "passive"))
      (node (ref "Q1") (pin "3") (pinfunction "C_3") (pintype "passive"))
      (node (ref "R9") (pin "1") (pinfunction "1_1") (pintype "passive"))
      (node (ref "U1") (pin "3") (pinfunction "EN_3") (pintype "bidirectional"))
    )
    (net (code "47") (name "RXI") (class "Default")
      (node (ref "D9") (pin "C") (pinfunction "C_C") (pintype "passive"))
      (node (ref "U1") (pin "34") (pinfunction "RXD_34") (pintype "bidirectional"))
      (node (ref "U3") (pin "2") (pinfunction "TXO_2") (pintype "bidirectional"))
    )
    (net (code "48") (name "SHIELD") (class "Default")
      (node (ref "J1") (pin "SHIELD") (pinfunction "SHIELD_SHIELD") (pintype "bidirectional"))
      (node (ref "J1") (pin "SHIELD10") (pinfunction "SHIELD_SHIELD10") (pintype "bidirectional"))
      (node (ref "J1") (pin "SHIELD2") (pinfunction "SHIELD_SHIELD2") (pintype "bidirectional"))
      (node (ref "J1") (pin "SHIELD3") (pinfunction "SHIELD_SHIELD3") (pintype "bidirectional"))
      (node (ref "J1") (pin "SHIELD4") (pinfunction "SHIELD_SHIELD4") (pintype "bidirectional"))
      (node (ref "J1") (pin "SHIELD5") (pinfunction "SHIELD_SHIELD5") (pintype "bidirectional"))
      (node (ref "J1") (pin "SHIELD6") (pinfunction "SHIELD_SHIELD6") (pintype "bidirectional"))
      (node (ref "J1") (pin "SHIELD7") (pinfunction "SHIELD_SHIELD7") (pintype "bidirectional"))
      (node (ref "J1") (pin "SHIELD8") (pinfunction "SHIELD_SHIELD8") (pintype "bidirectional"))
      (node (ref "J1") (pin "SHIELD9") (pinfunction "SHIELD_SHIELD9") (pintype "bidirectional"))
    )
    (net (code "49") (name "SHTDWN") (class "Default")
      (node (ref "Q4") (pin "3") (pinfunction "D_3") (pintype "bidirectional"))
      (node (ref "R6") (pin "1") (pinfunction "1_1") (pintype "passive"))
    )
    (net (code "50") (name "SHTDWN_BASE") (class "Default")
      (node (ref "D4") (pin "C") (pinfunction "C_C") (pintype "passive"))
      (node (ref "U$4") (pin "3") (pinfunction "CTL_3") (pintype "bidirectional"))
    )
    (net (code "51") (name "TXO") (class "Default")
      (node (ref "D8") (pin "C") (pinfunction "C_C") (pintype "passive"))
      (node (ref "U1") (pin "35") (pinfunction "TXD_35") (pintype "bidirectional"))
      (node (ref "U3") (pin "3") (pinfunction "RXI_3") (pintype "bidirectional"))
    )
    (net (code "52") (name "VCC") (class "Default")
      (node (ref "J2") (pin "1") (pinfunction "1_1") (pintype "passive"))
      (node (ref "J5") (pin "2") (pinfunction "2_2") (pintype "passive"))
      (node (ref "J8") (pin "1") (pinfunction "1_1") (pintype "passive"))
      (node (ref "Q4") (pin "2") (pinfunction "S_2") (pintype "bidirectional"))
    )
    (net (code "53") (name "VCC_SWITCHED") (class "Default")
      (node (ref "C5") (pin "1") (pinfunction "1_1") (pintype "passive"))
      (node (ref "J3") (pin "1") (pinfunction "1_1") (pintype "passive"))
      (node (ref "U$4") (pin "2") (pinfunction "VIN+_2") (pintype "bidirectional"))
    )
    (net (code "54") (name "VREFH") (class "Default")
      (node (ref "C10") (pin "1") (pinfunction "1_1") (pintype "passive"))
      (node (ref "C13") (pin "1") (pinfunction "1_1") (pintype "passive"))
      (node (ref "C15") (pin "1") (pinfunction "1_1") (pintype "passive"))
      (node (ref "JP2") (pin "2") (pinfunction "2_2") (pintype "passive"))
      (node (ref "R30") (pin "2") (pinfunction "2_2") (pintype "passive"))
      (node (ref "U$1") (pin "5") (pinfunction "VREFH-F_5") (pintype "bidirectional"))
      (node (ref "U$1") (pin "6") (pinfunction "VREFH-S_6") (pintype "bidirectional"))
      (node (ref "U$2") (pin "5") (pinfunction "VREFH-F_5") (pintype "bidirectional"))
      (node (ref "U$2") (pin "6") (pinfunction "VREFH-S_6") (pintype "bidirectional"))
    )
    (net (code "55") (name "VREFL") (class "Default")
      (node (ref "C11") (pin "1") (pinfunction "1_1") (pintype "passive"))
      (node (ref "C12") (pin "1") (pinfunction "1_1") (pintype "passive"))
      (node (ref "C14") (pin "1") (pinfunction "1_1") (pintype "passive"))
      (node (ref "JP3") (pin "2") (pinfunction "2_2") (pintype "passive"))
      (node (ref "R31") (pin "2") (pinfunction "2_2") (pintype "passive"))
      (node (ref "U$1") (pin "7") (pinfunction "VREFL-S_7") (pintype "bidirectional"))
      (node (ref "U$1") (pin "8") (pinfunction "VREFL-F_8") (pintype "bidirectional"))
      (node (ref "U$2") (pin "7") (pinfunction "VREFL-S_7") (pintype "bidirectional"))
      (node (ref "U$2") (pin "8") (pinfunction "VREFL-F_8") (pintype "bidirectional"))
    )
    (net (code "56") (name "V_USB") (class "Default")
      (node (ref "D7") (pin "A") (pinfunction "A_A") (pintype "passive"))
      (node (ref "J1") (pin "VBUS") (pinfunction "VBUS_VBUS") (pintype "power_in"))
    )
    (net (code "57") (name "unconnected-(J1-PadID)") (class "Default")
      (node (ref "J1") (pin "ID") (pinfunction "ID_ID") (pintype "bidirectional"))
    )
    (net (code "58") (name "unconnected-(U1-CS0_V{slash}IO5-Pad29)") (class "Default")
      (node (ref "U1") (pin "29") (pinfunction "CS0_V/IO5_29") (pintype "bidirectional"))
    )
    (net (code "59") (name "unconnected-(U1-IO2-Pad24)") (class "Default")
      (node (ref "U1") (pin "24") (pinfunction "IO2_24") (pintype "bidirectional"))
    )
    (net (code "60") (name "unconnected-(U1-IO4-Pad26)") (class "Default")
      (node (ref "U1") (pin "26") (pinfunction "IO4_26") (pintype "bidirectional"))
    )
    (net (code "61") (name "unconnected-(U1-IO34-Pad6)") (class "Default")
      (node (ref "U1") (pin "6") (pinfunction "IO34_6") (pintype "bidirectional"))
    )
    (net (code "62") (name "unconnected-(U1-IO35-Pad7)") (class "Default")
      (node (ref "U1") (pin "7") (pinfunction "IO35_7") (pintype "bidirectional"))
    )
    (net (code "63") (name "unconnected-(U1-MISO_H{slash}IO12-Pad14)") (class "Default")
      (node (ref "U1") (pin "14") (pinfunction "MISO_H/IO12_14") (pintype "bidirectional"))
    )
    (net (code "64") (name "unconnected-(U1-NC-Pad32)") (class "Default")
      (node (ref "U1") (pin "32") (pinfunction "NC_32") (pintype "bidirectional"))
    )
    (net (code "65") (name "unconnected-(U1-SCK{slash}IO6-Pad20)") (class "Default")
      (node (ref "U1") (pin "20") (pinfunction "SCK/IO6_20") (pintype "bidirectional"))
    )
    (net (code "66") (name "unconnected-(U1-SCS{slash}IO11-Pad19)") (class "Default")
      (node (ref "U1") (pin "19") (pinfunction "SCS/IO11_19") (pintype "bidirectional"))
    )
    (net (code "67") (name "unconnected-(U1-SDI{slash}IO8-Pad22)") (class "Default")
      (node (ref "U1") (pin "22") (pinfunction "SDI/IO8_22") (pintype "bidirectional"))
    )
    (net (code "68") (name "unconnected-(U1-SDO{slash}IO7-Pad21)") (class "Default")
      (node (ref "U1") (pin "21") (pinfunction "SDO/IO7_21") (pintype "bidirectional"))
    )
    (net (code "69") (name "unconnected-(U1-SENSOR_VN{slash}I39-Pad5)") (class "Default")
      (node (ref "U1") (pin "5") (pinfunction "SENSOR_VN/I39_5") (pintype "bidirectional"))
    )
    (net (code "70") (name "unconnected-(U1-SENSOR_VP{slash}I36-Pad4)") (class "Default")
      (node (ref "U1") (pin "4") (pinfunction "SENSOR_VP/I36_4") (pintype "bidirectional"))
    )
    (net (code "71") (name "unconnected-(U1-SHD{slash}IO9-Pad17)") (class "Default")
      (node (ref "U1") (pin "17") (pinfunction "SHD/IO9_17") (pintype "bidirectional"))
    )
    (net (code "72") (name "unconnected-(U1-SWP{slash}IO10-Pad18)") (class "Default")
      (node (ref "U1") (pin "18") (pinfunction "SWP/IO10_18") (pintype "bidirectional"))
    )
    (net (code "73") (name "unconnected-(U1-XTAL_N{slash}IO33-Pad9)") (class "Default")
      (node (ref "U1") (pin "9") (pinfunction "XTAL_N/IO33_9") (pintype "bidirectional"))
    )
    (net (code "74") (name "unconnected-(U1-XTAL_P{slash}IO32-Pad8)") (class "Default")
      (node (ref "U1") (pin "8") (pinfunction "XTAL_P/IO32_8") (pintype "bidirectional"))
    )
    (net (code "75") (name "unconnected-(U2-NC-Pad4)") (class "Default")
      (node (ref "U2") (pin "4") (pinfunction "NC_4") (pintype "no_connect"))
    )
    (net (code "76") (name "unconnected-(U3-R232-Pad15)") (class "Default")
      (node (ref "U3") (pin "15") (pinfunction "R232_15") (pintype "bidirectional"))
    )
    (net (code "77") (name "unconnected-(U3-~{CTS}-Pad9)") (class "Default")
      (node (ref "U3") (pin "9") (pinfunction "~{CTS}_9") (pintype "bidirectional"))
    )
    (net (code "78") (name "unconnected-(U3-~{DCD}-Pad12)") (class "Default")
      (node (ref "U3") (pin "12") (pinfunction "~{DCD}_12") (pintype "bidirectional"))
    )
    (net (code "79") (name "unconnected-(U3-~{DSR}-Pad10)") (class "Default")
      (node (ref "U3") (pin "10") (pinfunction "~{DSR}_10") (pintype "bidirectional"))
    )
    (net (code "80") (name "unconnected-(U3-~{RI}-Pad11)") (class "Default")
      (node (ref "U3") (pin "11") (pinfunction "~{RI}_11") (pintype "bidirectional"))
    )
  )
)
